# PrototypeBoardV2D.net
KiCad netlist of a schematic drawn in EasyEDA Pro
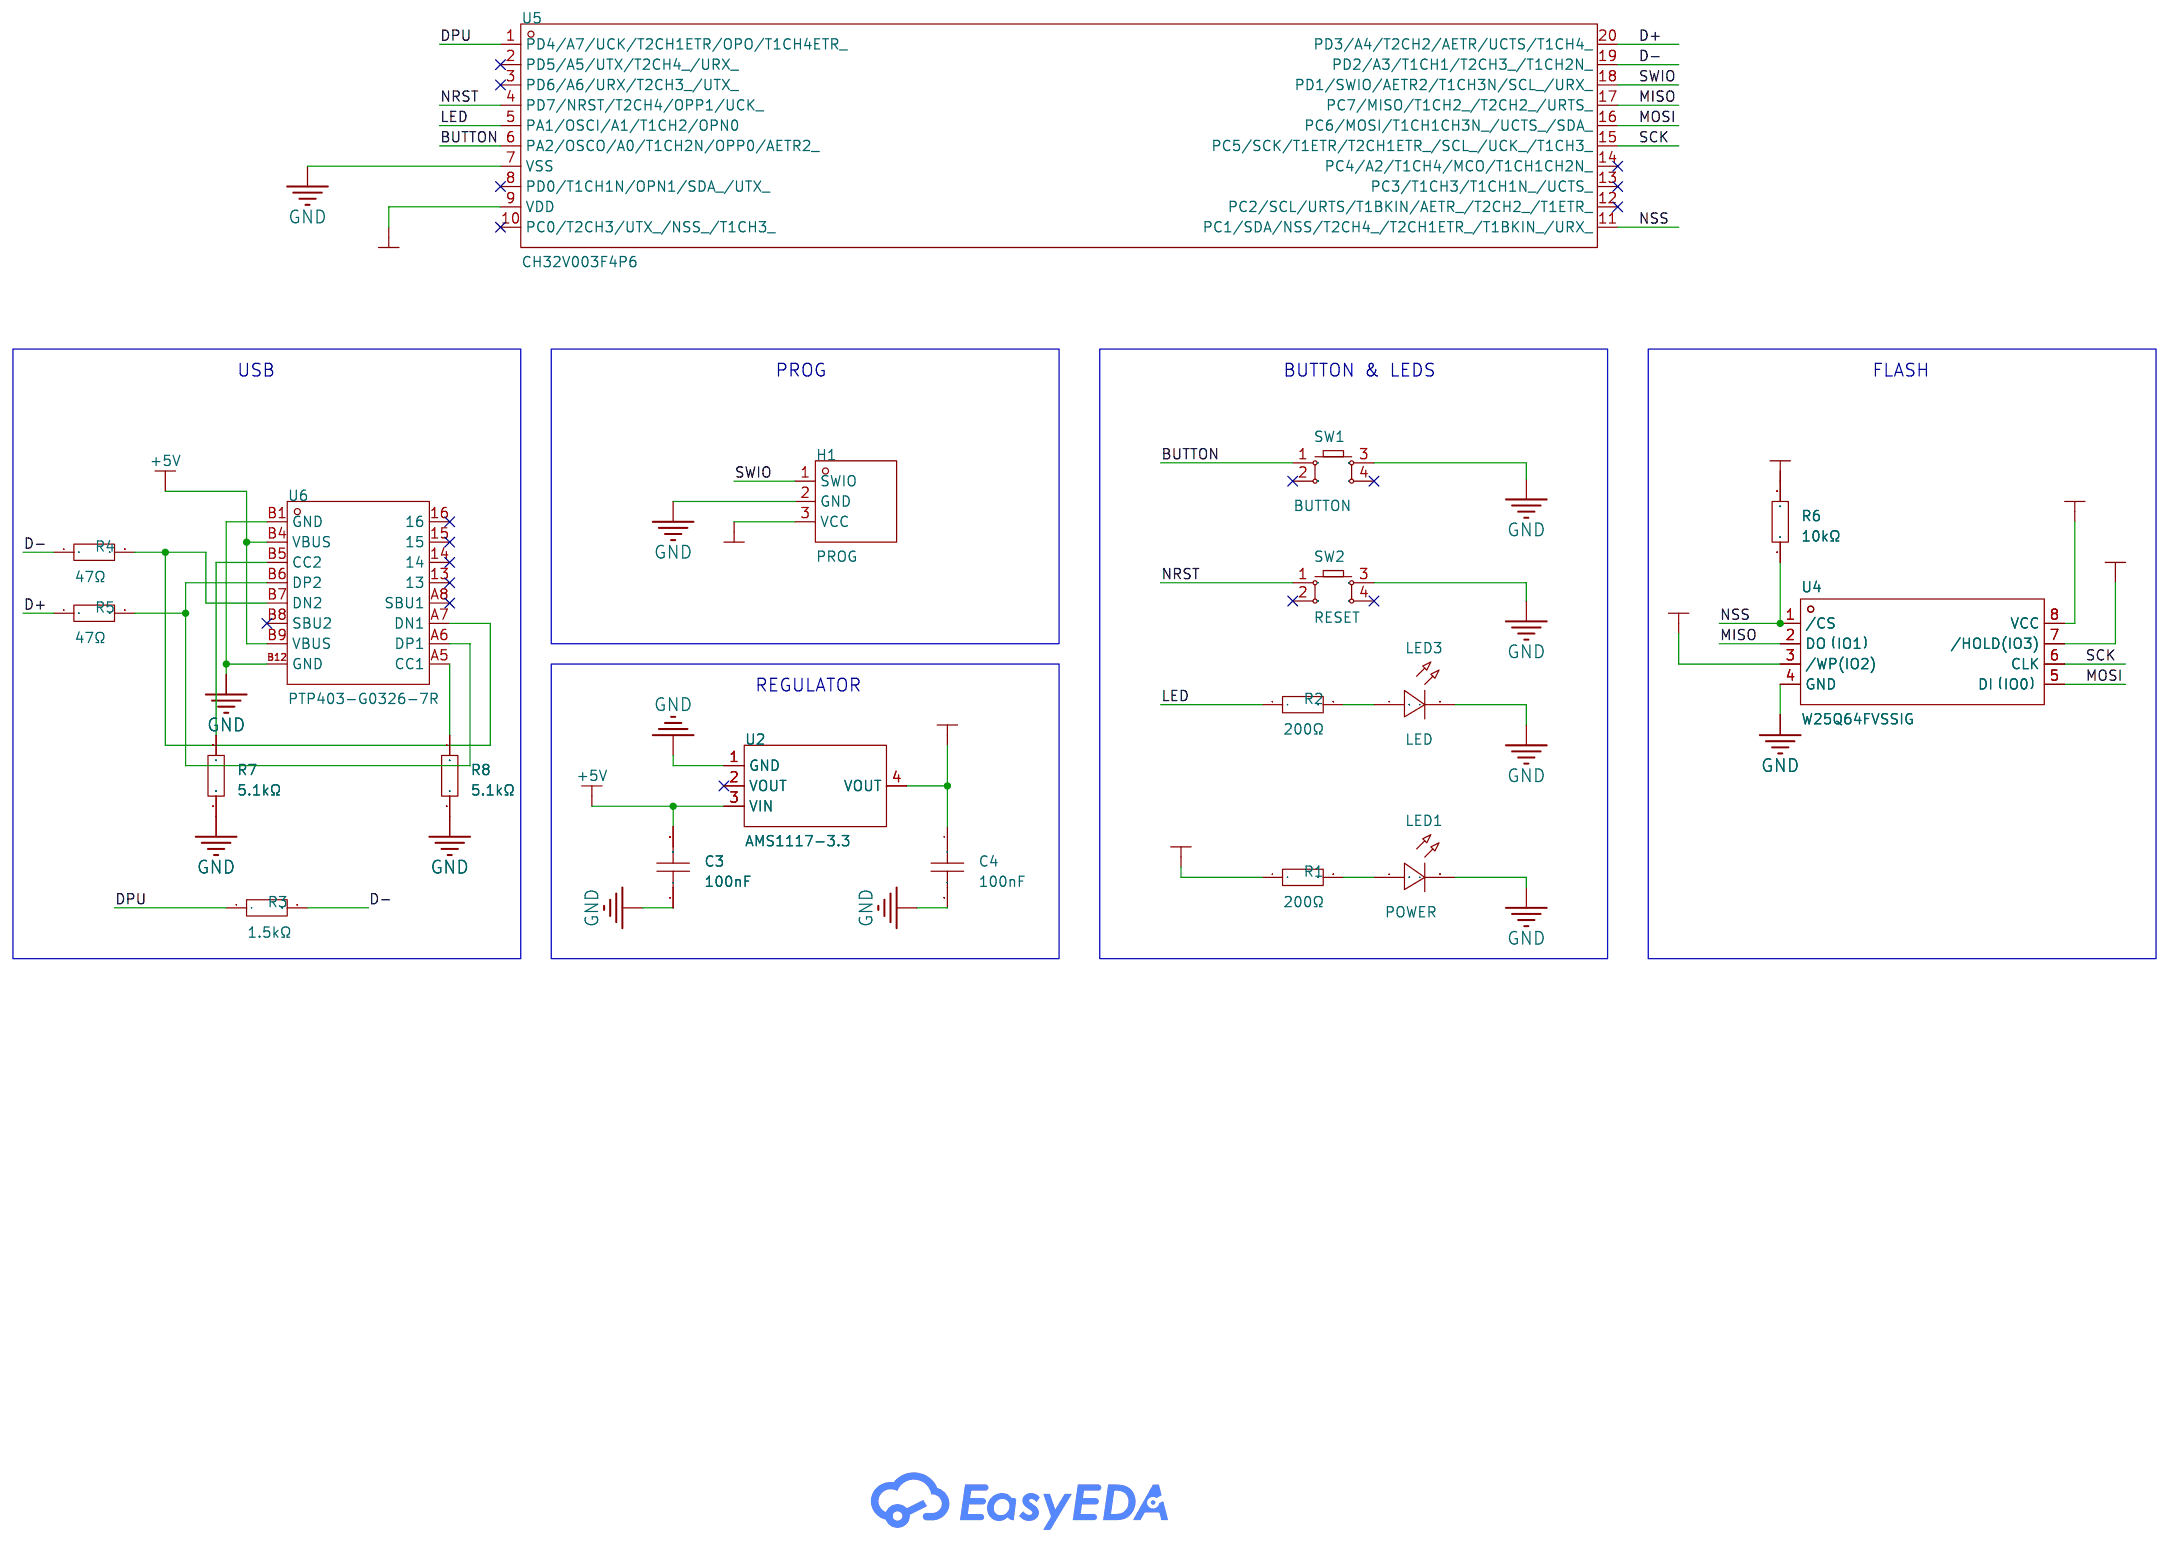
[diagram p0: schematic sheet]

(export (version "E")
  (design (tool "Eeschema 10.0.6"))
  (components
    (comp (ref "C3")
      (value "100nF")
      (footprint "easyedapro:CAP-TH_L5.8-W3.0-P4.7-D0.45")
      (fields (field (name "Manufacturer Part") "1C10Z5U104M050B") (field (name "Manufacturer") "VISHAY(威世)"))
      (libsource (lib "easyedapro") (part "1C10Z5U104M050B"))
    )
    (comp (ref "C4")
      (value "100nF")
      (footprint "easyedapro:CAP-TH_L5.8-W3.0-P4.7-D0.45")
      (fields (field (name "Manufacturer Part") "1C10Z5U104M050B") (field (name "Manufacturer") "VISHAY(威世)"))
      (libsource (lib "easyedapro") (part "1C10Z5U104M050B"))
    )
    (comp (ref "H1")
      (value "PROG")
      (footprint "easyedapro:HDR-TH_3P-P2.54-V-M")
      (libsource (lib "easyedapro") (part "PZ254V-11-03P_C2937625"))
    )
    (comp (ref "LED1")
      (value "POWER")
      (footprint "easyedapro:LED-TH_BD3.0-P2.54-FD")
      (libsource (lib "easyedapro") (part "LED_TH-R"))
    )
    (comp (ref "LED3")
      (value "LED")
      (footprint "easyedapro:LED-TH_BD5.0-P2.54-L-RD_WHITE")
      (libsource (lib "easyedapro") (part "LED_TH-B"))
    )
    (comp (ref "R1")
      (value "200Ω")
      (footprint "easyedapro:R1206")
      (libsource (lib "easyedapro") (part "Res"))
    )
    (comp (ref "R2")
      (value "200Ω")
      (footprint "easyedapro:R1206")
      (libsource (lib "easyedapro") (part "Res"))
    )
    (comp (ref "R3")
      (value "1.5kΩ")
      (footprint "easyedapro:R1206")
      (libsource (lib "easyedapro") (part "Res"))
    )
    (comp (ref "R4") (value "47Ω") (footprint "easyedapro:R1206") (libsource (lib "easyedapro") (part "Res")))
    (comp (ref "R5") (value "47Ω") (footprint "easyedapro:R1206") (libsource (lib "easyedapro") (part "Res")))
    (comp (ref "R6")
      (value "10kΩ")
      (footprint "easyedapro:R1206")
      (libsource (lib "easyedapro") (part "Res"))
    )
    (comp (ref "R7")
      (value "5.1kΩ")
      (footprint "easyedapro:R1206")
      (libsource (lib "easyedapro") (part "Res"))
    )
    (comp (ref "R8")
      (value "5.1kΩ")
      (footprint "easyedapro:R1206")
      (libsource (lib "easyedapro") (part "Res"))
    )
    (comp (ref "SW1")
      (value "BUTTON")
      (footprint "easyedapro:KEY-TH_4P-L6.0-W6.0-P3.90-LS6.5")
      (libsource (lib "easyedapro") (part "轻触按键"))
    )
    (comp (ref "SW2")
      (value "RESET")
      (footprint "easyedapro:KEY-TH_4P-L6.0-W6.0-P3.90-LS6.5")
      (libsource (lib "easyedapro") (part "轻触按键"))
    )
    (comp (ref "U2")
      (value "AMS1117-3.3")
      (footprint "easyedapro:SOT-223-3_L6.5-W3.4-P2.30-LS7.0-BR")
      (fields (field (name "Manufacturer") "AMS"))
      (libsource (lib "easyedapro") (part "AMS1117-3.3"))
    )
    (comp (ref "U4")
      (value "W25Q64FVSSIG")
      (footprint "easyedapro:SOIC-8_L5.3-W5.3-P1.27-LS8.0-BL")
      (libsource (lib "easyedapro") (part "W25Q64FVSSIG_C66141"))
    )
    (comp (ref "U5")
      (value "CH32V003F4P6")
      (footprint "easyedapro:TSSOP-20_L6.5-W4.4-P0.65-LS6.4-BL")
      (fields (field (name "Manufacturer") "WCH(南京沁恒)"))
      (libsource (lib "easyedapro") (part "CH32V003F4P6"))
    )
    (comp (ref "U6")
      (value "PTP403-G0326-7R")
      (footprint "easyedapro:USB-SMD_PTP403-G0326-7R")
      (libsource (lib "easyedapro") (part "USB Type-C 16P"))
    )
  )
  (nets
    (net (code "1") (name "+3.3V") (class "Default")
      (node (ref "C4") (pin "1") (pinfunction "1_1") (pintype "unspecified"))
      (node (ref "H1") (pin "3") (pinfunction "VCC_3") (pintype "unspecified"))
      (node (ref "R1") (pin "1") (pinfunction "1_1") (pintype "input"))
      (node (ref "R6") (pin "2") (pinfunction "2_2") (pintype "input"))
      (node (ref "U2") (pin "4") (pinfunction "VOUT_4") (pintype "unspecified"))
      (node (ref "U4") (pin "3") (pinfunction "/WP(IO2)_3") (pintype "unspecified"))
      (node (ref "U4") (pin "7") (pinfunction "/HOLD(IO3)_7") (pintype "unspecified"))
      (node (ref "U4") (pin "8") (pinfunction "VCC_8") (pintype "unspecified"))
      (node (ref "U5") (pin "9") (pinfunction "VDD_9") (pintype "unspecified"))
    )
    (net (code "2") (name "+5V") (class "Default")
      (node (ref "C3") (pin "2") (pinfunction "2_2") (pintype "unspecified"))
      (node (ref "U2") (pin "3") (pinfunction "VIN_3") (pintype "unspecified"))
      (node (ref "U6") (pin "B4") (pinfunction "VBUS_B4") (pintype "input"))
      (node (ref "U6") (pin "B9") (pinfunction "VBUS_B9") (pintype "input"))
    )
    (net (code "3") (name "/BUTTON") (class "Default")
      (node (ref "SW1") (pin "1") (pinfunction "1_1") (pintype "input"))
      (node (ref "U5") (pin "6") (pinfunction "PA2/OSCO/A0/T1CH2N/OPP0/AETR2__6") (pintype "unspecified"))
    )
    (net (code "4") (name "/D+") (class "Default")
      (node (ref "R5") (pin "1") (pinfunction "1_1") (pintype "input"))
      (node (ref "U5") (pin "20") (pinfunction "PD3/A4/T2CH2/AETR/UCTS/T1CH4__20") (pintype "unspecified"))
    )
    (net (code "5") (name "/D-") (class "Default")
      (node (ref "R3") (pin "2") (pinfunction "2_2") (pintype "input"))
      (node (ref "R4") (pin "1") (pinfunction "1_1") (pintype "input"))
      (node (ref "U5") (pin "19") (pinfunction "PD2/A3/T1CH1/T2CH3_/T1CH2N__19") (pintype "unspecified"))
    )
    (net (code "6") (name "/DPU") (class "Default")
      (node (ref "R3") (pin "1") (pinfunction "1_1") (pintype "input"))
      (node (ref "U5") (pin "1") (pinfunction "PD4/A7/UCK/T2CH1ETR/OPO/T1CH4ETR__1") (pintype "unspecified"))
    )
    (net (code "7") (name "/LED") (class "Default")
      (node (ref "R2") (pin "1") (pinfunction "1_1") (pintype "input"))
      (node (ref "U5") (pin "5") (pinfunction "PA1/OSCI/A1/T1CH2/OPN0_5") (pintype "unspecified"))
    )
    (net (code "8") (name "/MISO") (class "Default")
      (node (ref "U4") (pin "2") (pinfunction "DO（IO1）_2") (pintype "unspecified"))
      (node (ref "U5") (pin "17") (pinfunction "PC7/MISO/T1CH2_/T2CH2_/URTS__17") (pintype "unspecified"))
    )
    (net (code "9") (name "/MOSI") (class "Default")
      (node (ref "U4") (pin "5") (pinfunction "DI（IO0）_5") (pintype "unspecified"))
      (node (ref "U5") (pin "16") (pinfunction "PC6/MOSI/T1CH1CH3N_/UCTS_/SDA__16") (pintype "unspecified"))
    )
    (net (code "10") (name "/NRST") (class "Default")
      (node (ref "SW2") (pin "1") (pinfunction "1_1") (pintype "input"))
      (node (ref "U5") (pin "4") (pinfunction "PD7/NRST/T2CH4/OPP1/UCK__4") (pintype "unspecified"))
    )
    (net (code "11") (name "/NSS") (class "Default")
      (node (ref "R6") (pin "1") (pinfunction "1_1") (pintype "input"))
      (node (ref "U4") (pin "1") (pinfunction "/CS_1") (pintype "unspecified"))
      (node (ref "U5") (pin "11") (pinfunction "PC1/SDA/NSS/T2CH4_/T2CH1ETR_/T1BKIN_/URX__11") (pintype "unspecified"))
    )
    (net (code "12") (name "/SCK") (class "Default")
      (node (ref "U4") (pin "6") (pinfunction "CLK_6") (pintype "unspecified"))
      (node (ref "U5") (pin "15") (pinfunction "PC5/SCK/T1ETR/T2CH1ETR_/SCL_/UCK_/T1CH3__15") (pintype "unspecified"))
    )
    (net (code "13") (name "/SWIO") (class "Default")
      (node (ref "H1") (pin "1") (pinfunction "SWIO_1") (pintype "unspecified"))
      (node (ref "U5") (pin "18") (pinfunction "PD1/SWIO/AETR2/T1CH3N/SCL_/URX__18") (pintype "unspecified"))
    )
    (net (code "14") (name "GND") (class "Default")
      (node (ref "C3") (pin "1") (pinfunction "1_1") (pintype "unspecified"))
      (node (ref "C4") (pin "2") (pinfunction "2_2") (pintype "unspecified"))
      (node (ref "H1") (pin "2") (pinfunction "GND_2") (pintype "unspecified"))
      (node (ref "LED1") (pin "2") (pinfunction "A_2") (pintype "input"))
      (node (ref "LED3") (pin "2") (pinfunction "A_2") (pintype "input"))
      (node (ref "R7") (pin "1") (pinfunction "1_1") (pintype "input"))
      (node (ref "R8") (pin "1") (pinfunction "1_1") (pintype "input"))
      (node (ref "SW1") (pin "3") (pinfunction "3_3") (pintype "input"))
      (node (ref "SW2") (pin "3") (pinfunction "3_3") (pintype "input"))
      (node (ref "U2") (pin "1") (pinfunction "GND_1") (pintype "unspecified"))
      (node (ref "U4") (pin "4") (pinfunction "GND_4") (pintype "unspecified"))
      (node (ref "U5") (pin "7") (pinfunction "VSS_7") (pintype "unspecified"))
      (node (ref "U6") (pin "B1") (pinfunction "GND_B1") (pintype "input"))
      (node (ref "U6") (pin "B12") (pinfunction "GND_B12") (pintype "input"))
    )
    (net (code "15") (name "Net-(LED1-C)") (class "Default")
      (node (ref "LED1") (pin "1") (pinfunction "C_1") (pintype "input"))
      (node (ref "R1") (pin "2") (pinfunction "2_2") (pintype "input"))
    )
    (net (code "16") (name "Net-(LED3-C)") (class "Default")
      (node (ref "LED3") (pin "1") (pinfunction "C_1") (pintype "input"))
      (node (ref "R2") (pin "2") (pinfunction "2_2") (pintype "input"))
    )
    (net (code "17") (name "Net-(U6-CC1)") (class "Default")
      (node (ref "R8") (pin "2") (pinfunction "2_2") (pintype "input"))
      (node (ref "U6") (pin "A5") (pinfunction "CC1_A5") (pintype "input"))
    )
    (net (code "18") (name "Net-(U6-CC2)") (class "Default")
      (node (ref "R7") (pin "2") (pinfunction "2_2") (pintype "input"))
      (node (ref "U6") (pin "B5") (pinfunction "CC2_B5") (pintype "input"))
    )
    (net (code "19") (name "Net-(U6-DN1)") (class "Default")
      (node (ref "R4") (pin "2") (pinfunction "2_2") (pintype "input"))
      (node (ref "U6") (pin "A7") (pinfunction "DN1_A7") (pintype "input"))
      (node (ref "U6") (pin "B7") (pinfunction "DN2_B7") (pintype "input"))
    )
    (net (code "20") (name "Net-(U6-DP1)") (class "Default")
      (node (ref "R5") (pin "2") (pinfunction "2_2") (pintype "input"))
      (node (ref "U6") (pin "A6") (pinfunction "DP1_A6") (pintype "input"))
      (node (ref "U6") (pin "B6") (pinfunction "DP2_B6") (pintype "input"))
    )
    (net (code "21") (name "unconnected-(SW1-Pad2)") (class "Default")
      (node (ref "SW1") (pin "2") (pinfunction "2_2") (pintype "input+no_connect"))
    )
    (net (code "22") (name "unconnected-(SW1-Pad4)") (class "Default")
      (node (ref "SW1") (pin "4") (pinfunction "4_4") (pintype "input+no_connect"))
    )
    (net (code "23") (name "unconnected-(SW2-Pad2)") (class "Default")
      (node (ref "SW2") (pin "2") (pinfunction "2_2") (pintype "input+no_connect"))
    )
    (net (code "24") (name "unconnected-(SW2-Pad4)") (class "Default")
      (node (ref "SW2") (pin "4") (pinfunction "4_4") (pintype "input+no_connect"))
    )
    (net (code "25") (name "unconnected-(U2-VOUT-Pad2)") (class "Default")
      (node (ref "U2") (pin "2") (pinfunction "VOUT_2") (pintype "unspecified+no_connect"))
    )
    (net (code "26") (name "unconnected-(U5-PC0{slash}T2CH3{slash}UTX_{slash}NSS_{slash}T1CH3_-Pad10)") (class "Default")
      (node (ref "U5") (pin "10") (pinfunction "PC0/T2CH3/UTX_/NSS_/T1CH3__10") (pintype "unspecified+no_connect"))
    )
    (net (code "27") (name "unconnected-(U5-PC2{slash}SCL{slash}URTS{slash}T1BKIN{slash}AETR_{slash}T2CH2_{slash}T1ETR_-Pad12)") (class "Default")
      (node (ref "U5") (pin "12") (pinfunction "PC2/SCL/URTS/T1BKIN/AETR_/T2CH2_/T1ETR__12") (pintype "unspecified+no_connect"))
    )
    (net (code "28") (name "unconnected-(U5-PC3{slash}T1CH3{slash}T1CH1N_{slash}UCTS_-Pad13)") (class "Default")
      (node (ref "U5") (pin "13") (pinfunction "PC3/T1CH3/T1CH1N_/UCTS__13") (pintype "unspecified+no_connect"))
    )
    (net (code "29") (name "unconnected-(U5-PC4{slash}A2{slash}T1CH4{slash}MCO{slash}T1CH1CH2N_-Pad14)") (class "Default")
      (node (ref "U5") (pin "14") (pinfunction "PC4/A2/T1CH4/MCO/T1CH1CH2N__14") (pintype "unspecified+no_connect"))
    )
    (net (code "30") (name "unconnected-(U5-PD0{slash}T1CH1N{slash}OPN1{slash}SDA_{slash}UTX_-Pad8)") (class "Default")
      (node (ref "U5") (pin "8") (pinfunction "PD0/T1CH1N/OPN1/SDA_/UTX__8") (pintype "unspecified+no_connect"))
    )
    (net (code "31") (name "unconnected-(U5-PD5{slash}A5{slash}UTX{slash}T2CH4_{slash}URX_-Pad2)") (class "Default")
      (node (ref "U5") (pin "2") (pinfunction "PD5/A5/UTX/T2CH4_/URX__2") (pintype "unspecified+no_connect"))
    )
    (net (code "32") (name "unconnected-(U5-PD6{slash}A6{slash}URX{slash}T2CH3_{slash}UTX_-Pad3)") (class "Default")
      (node (ref "U5") (pin "3") (pinfunction "PD6/A6/URX/T2CH3_/UTX__3") (pintype "unspecified+no_connect"))
    )
    (net (code "33") (name "unconnected-(U6-Pad13)") (class "Default")
      (node (ref "U6") (pin "13") (pinfunction "13_13") (pintype "input+no_connect"))
    )
    (net (code "34") (name "unconnected-(U6-Pad14)") (class "Default")
      (node (ref "U6") (pin "14") (pinfunction "14_14") (pintype "input+no_connect"))
    )
    (net (code "35") (name "unconnected-(U6-Pad15)") (class "Default")
      (node (ref "U6") (pin "15") (pinfunction "15_15") (pintype "input+no_connect"))
    )
    (net (code "36") (name "unconnected-(U6-Pad16)") (class "Default")
      (node (ref "U6") (pin "16") (pinfunction "16_16") (pintype "input+no_connect"))
    )
    (net (code "37") (name "unconnected-(U6-SBU1-PadA8)") (class "Default")
      (node (ref "U6") (pin "A8") (pinfunction "SBU1_A8") (pintype "input+no_connect"))
    )
    (net (code "38") (name "unconnected-(U6-SBU2-PadB8)") (class "Default")
      (node (ref "U6") (pin "B8") (pinfunction "SBU2_B8") (pintype "input+no_connect"))
    )
  )
)
